# miconborad.net
KiCad netlist of a schematic drawn in EAGLE
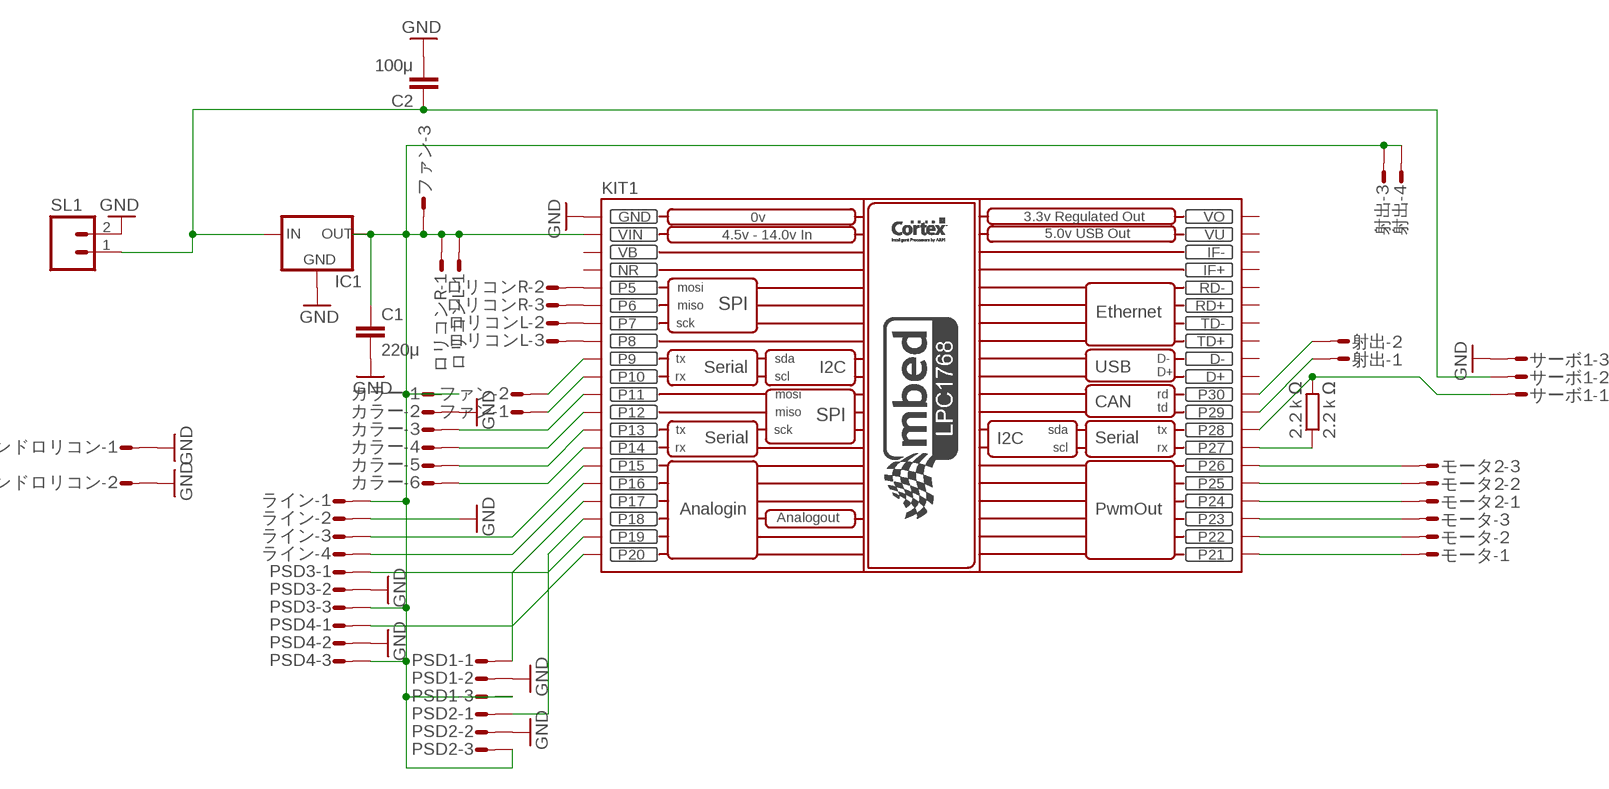
[diagram p0: schematic, sheet 1]

(export (version "E")
  (design (tool "Eeschema 10.0.6"))
  (components
    (comp (ref "2.2ｋΩ")
      (value "2.2ｋΩ")
      (footprint "eagle-import:0204V")
      (libsource (lib "eagle-import") (part "R-EU_0204/2V"))
    )
    (comp (ref "C1")
      (value "220μ")
      (footprint "eagle-import:C025-024X044")
      (libsource (lib "eagle-import") (part "C-EU025-024X044"))
    )
    (comp (ref "C2")
      (value "100μ")
      (footprint "eagle-import:C025-024X044")
      (libsource (lib "eagle-import") (part "C-EU025-024X044"))
    )
    (comp (ref "IC1")
      (value "78XX_V")
      (footprint "eagle-import:78XXV")
      (libsource (lib "eagle-import") (part "78XX_V"))
    )
    (comp (ref "KIT1")
      (value "MBED_NXP_LPC1768")
      (footprint "eagle-import:MBED-KIT")
      (libsource (lib "eagle-import") (part "MBED_NXP_LPC1768"))
    )
    (comp (ref "PSD1")
      (value "S03P")
      (footprint "eagle-import:S03P")
      (libsource (lib "eagle-import") (part "S03P"))
    )
    (comp (ref "PSD2")
      (value "S03P")
      (footprint "eagle-import:S03P")
      (libsource (lib "eagle-import") (part "S03P"))
    )
    (comp (ref "PSD3")
      (value "S03P")
      (footprint "eagle-import:S03P")
      (libsource (lib "eagle-import") (part "S03P"))
    )
    (comp (ref "PSD4")
      (value "S03P")
      (footprint "eagle-import:S03P")
      (libsource (lib "eagle-import") (part "S03P"))
    )
    (comp (ref "SL1")
      (value "M02")
      (footprint "eagle-import:02P")
      (libsource (lib "eagle-import") (part "M02"))
    )
    (comp (ref "カラー")
      (value "S06P")
      (footprint "eagle-import:S06P")
      (libsource (lib "eagle-import") (part "S06P"))
    )
    (comp (ref "グランドロリコン")
      (value "S02P")
      (footprint "eagle-import:S02P")
      (libsource (lib "eagle-import") (part "S02P"))
    )
    (comp (ref "サーボ1")
      (value "S03P")
      (footprint "eagle-import:S03P")
      (libsource (lib "eagle-import") (part "S03P"))
    )
    (comp (ref "ファン")
      (value "S03P")
      (footprint "eagle-import:S03P")
      (libsource (lib "eagle-import") (part "S03P"))
    )
    (comp (ref "モータ")
      (value "S03P")
      (footprint "eagle-import:S03P")
      (libsource (lib "eagle-import") (part "S03P"))
    )
    (comp (ref "モータ2")
      (value "S03P")
      (footprint "eagle-import:S03P")
      (libsource (lib "eagle-import") (part "S03P"))
    )
    (comp (ref "ライン")
      (value "S04P")
      (footprint "eagle-import:S04P")
      (libsource (lib "eagle-import") (part "S04P"))
    )
    (comp (ref "ロリコンL")
      (value "S03P")
      (footprint "eagle-import:S03P")
      (libsource (lib "eagle-import") (part "S03P"))
    )
    (comp (ref "ロリコンR")
      (value "S03P")
      (footprint "eagle-import:S03P")
      (libsource (lib "eagle-import") (part "S03P"))
    )
    (comp (ref "射出")
      (value "S04P")
      (footprint "eagle-import:S04P")
      (libsource (lib "eagle-import") (part "S04P"))
    )
  )
  (nets
    (net (code "1") (name "/NR") (class "Default")
      (node (ref "KIT1") (pin "P$4") (pinfunction "NR_P$4") (pintype "power_in"))
    )
    (net (code "2") (name "/VB") (class "Default")
      (node (ref "KIT1") (pin "P$3") (pinfunction "VB_P$3") (pintype "power_in"))
    )
    (net (code "3") (name "/VO") (class "Default")
      (node (ref "KIT1") (pin "P$40") (pinfunction "VO_P$40") (pintype "power_in"))
    )
    (net (code "4") (name "/VU") (class "Default")
      (node (ref "KIT1") (pin "P$39") (pinfunction "VU_P$39") (pintype "power_in"))
    )
    (net (code "5") (name "GND") (class "Default")
      (node (ref "C1") (pin "2") (pinfunction "2_2") (pintype "passive"))
      (node (ref "C2") (pin "2") (pinfunction "2_2") (pintype "passive"))
      (node (ref "IC1") (pin "GND") (pinfunction "GND_GND") (pintype "input"))
      (node (ref "KIT1") (pin "P$1") (pinfunction "GND_P$1") (pintype "power_in"))
      (node (ref "PSD1") (pin "2") (pinfunction "S_2") (pintype "passive"))
      (node (ref "PSD2") (pin "2") (pinfunction "S_2") (pintype "passive"))
      (node (ref "PSD3") (pin "2") (pinfunction "S_2") (pintype "passive"))
      (node (ref "PSD4") (pin "2") (pinfunction "S_2") (pintype "passive"))
      (node (ref "SL1") (pin "2") (pinfunction "2_2") (pintype "passive"))
      (node (ref "カラー") (pin "2") (pinfunction "S_2") (pintype "passive"))
      (node (ref "グランドロリコン") (pin "1") (pinfunction "S_1") (pintype "passive"))
      (node (ref "グランドロリコン") (pin "2") (pinfunction "S_2") (pintype "passive"))
      (node (ref "サーボ1") (pin "3") (pinfunction "S_3") (pintype "passive"))
      (node (ref "ライン") (pin "2") (pinfunction "S_2") (pintype "passive"))
    )
    (net (code "6") (name "Net-(KIT1-P5)") (class "Default")
      (node (ref "KIT1") (pin "P$5") (pinfunction "P5_P$5") (pintype "bidirectional"))
      (node (ref "ロリコンR") (pin "2") (pinfunction "S_2") (pintype "passive"))
    )
    (net (code "7") (name "Net-(KIT1-P6)") (class "Default")
      (node (ref "KIT1") (pin "P$6") (pinfunction "P6_P$6") (pintype "bidirectional"))
      (node (ref "ロリコンR") (pin "3") (pinfunction "S_3") (pintype "passive"))
    )
    (net (code "8") (name "Net-(KIT1-P7)") (class "Default")
      (node (ref "KIT1") (pin "P$7") (pinfunction "P7_P$7") (pintype "bidirectional"))
      (node (ref "ロリコンL") (pin "2") (pinfunction "S_2") (pintype "passive"))
    )
    (net (code "9") (name "Net-(KIT1-P8)") (class "Default")
      (node (ref "KIT1") (pin "P$8") (pinfunction "P8_P$8") (pintype "bidirectional"))
      (node (ref "ロリコンL") (pin "3") (pinfunction "S_3") (pintype "passive"))
    )
    (net (code "10") (name "Net-(KIT1-P9)") (class "Default")
      (node (ref "KIT1") (pin "P$9") (pinfunction "P9_P$9") (pintype "bidirectional"))
      (node (ref "ファン") (pin "2") (pinfunction "S_2") (pintype "passive"))
    )
    (net (code "11") (name "Net-(KIT1-P10)") (class "Default")
      (node (ref "KIT1") (pin "P$10") (pinfunction "P10_P$10") (pintype "bidirectional"))
      (node (ref "ファン") (pin "1") (pinfunction "S_1") (pintype "passive"))
    )
    (net (code "12") (name "Net-(KIT1-P11)") (class "Default")
      (node (ref "KIT1") (pin "P$11") (pinfunction "P11_P$11") (pintype "bidirectional"))
      (node (ref "カラー") (pin "3") (pinfunction "S_3") (pintype "passive"))
    )
    (net (code "13") (name "Net-(KIT1-P12)") (class "Default")
      (node (ref "KIT1") (pin "P$12") (pinfunction "P12_P$12") (pintype "bidirectional"))
      (node (ref "カラー") (pin "4") (pinfunction "S_4") (pintype "passive"))
    )
    (net (code "14") (name "Net-(KIT1-P13)") (class "Default")
      (node (ref "KIT1") (pin "P$13") (pinfunction "P13_P$13") (pintype "bidirectional"))
      (node (ref "カラー") (pin "5") (pinfunction "S_5") (pintype "passive"))
    )
    (net (code "15") (name "Net-(KIT1-P14)") (class "Default")
      (node (ref "KIT1") (pin "P$14") (pinfunction "P14_P$14") (pintype "bidirectional"))
      (node (ref "カラー") (pin "6") (pinfunction "S_6") (pintype "passive"))
    )
    (net (code "16") (name "Net-(KIT1-P15)") (class "Default")
      (node (ref "KIT1") (pin "P$15") (pinfunction "P15_P$15") (pintype "bidirectional"))
      (node (ref "ライン") (pin "3") (pinfunction "S_3") (pintype "passive"))
    )
    (net (code "17") (name "Net-(KIT1-P16)") (class "Default")
      (node (ref "KIT1") (pin "P$16") (pinfunction "P16_P$16") (pintype "bidirectional"))
      (node (ref "ライン") (pin "4") (pinfunction "S_4") (pintype "passive"))
    )
    (net (code "18") (name "Net-(KIT1-P17)") (class "Default")
      (node (ref "KIT1") (pin "P$17") (pinfunction "P17_P$17") (pintype "bidirectional"))
      (node (ref "PSD1") (pin "1") (pinfunction "S_1") (pintype "passive"))
    )
    (net (code "19") (name "Net-(KIT1-P18)") (class "Default")
      (node (ref "KIT1") (pin "P$18") (pinfunction "P18_P$18") (pintype "bidirectional"))
      (node (ref "PSD2") (pin "1") (pinfunction "S_1") (pintype "passive"))
    )
    (net (code "20") (name "Net-(KIT1-P19)") (class "Default")
      (node (ref "KIT1") (pin "P$19") (pinfunction "P19_P$19") (pintype "bidirectional"))
      (node (ref "PSD3") (pin "1") (pinfunction "S_1") (pintype "passive"))
    )
    (net (code "21") (name "Net-(KIT1-P20)") (class "Default")
      (node (ref "KIT1") (pin "P$20") (pinfunction "P20_P$20") (pintype "bidirectional"))
      (node (ref "PSD4") (pin "1") (pinfunction "S_1") (pintype "passive"))
    )
    (net (code "22") (name "Net-(KIT1-P21)") (class "Default")
      (node (ref "KIT1") (pin "P$21") (pinfunction "P21_P$21") (pintype "bidirectional"))
      (node (ref "モータ") (pin "1") (pinfunction "S_1") (pintype "passive"))
    )
    (net (code "23") (name "Net-(KIT1-P22)") (class "Default")
      (node (ref "KIT1") (pin "P$22") (pinfunction "P22_P$22") (pintype "bidirectional"))
      (node (ref "モータ") (pin "2") (pinfunction "S_2") (pintype "passive"))
    )
    (net (code "24") (name "Net-(KIT1-P23)") (class "Default")
      (node (ref "KIT1") (pin "P$23") (pinfunction "P23_P$23") (pintype "bidirectional"))
      (node (ref "モータ") (pin "3") (pinfunction "S_3") (pintype "passive"))
    )
    (net (code "25") (name "Net-(KIT1-P24)") (class "Default")
      (node (ref "KIT1") (pin "P$24") (pinfunction "P24_P$24") (pintype "bidirectional"))
      (node (ref "モータ2") (pin "1") (pinfunction "S_1") (pintype "passive"))
    )
    (net (code "26") (name "Net-(KIT1-P25)") (class "Default")
      (node (ref "KIT1") (pin "P$25") (pinfunction "P25_P$25") (pintype "bidirectional"))
      (node (ref "モータ2") (pin "2") (pinfunction "S_2") (pintype "passive"))
    )
    (net (code "27") (name "Net-(KIT1-P26)") (class "Default")
      (node (ref "KIT1") (pin "P$26") (pinfunction "P26_P$26") (pintype "bidirectional"))
      (node (ref "モータ2") (pin "3") (pinfunction "S_3") (pintype "passive"))
    )
    (net (code "28") (name "Net-(KIT1-P27)") (class "Default")
      (node (ref "2.2ｋΩ") (pin "1") (pinfunction "1_1") (pintype "passive"))
      (node (ref "KIT1") (pin "P$27") (pinfunction "P27_P$27") (pintype "bidirectional"))
    )
    (net (code "29") (name "Net-(KIT1-P28)") (class "Default")
      (node (ref "2.2ｋΩ") (pin "2") (pinfunction "2_2") (pintype "passive"))
      (node (ref "KIT1") (pin "P$28") (pinfunction "P28_P$28") (pintype "bidirectional"))
      (node (ref "サーボ1") (pin "1") (pinfunction "S_1") (pintype "passive"))
    )
    (net (code "30") (name "Net-(KIT1-P29)") (class "Default")
      (node (ref "KIT1") (pin "P$29") (pinfunction "P29_P$29") (pintype "bidirectional"))
      (node (ref "射出") (pin "1") (pinfunction "S_1") (pintype "passive"))
    )
    (net (code "31") (name "Net-(KIT1-P30)") (class "Default")
      (node (ref "KIT1") (pin "P$30") (pinfunction "P30_P$30") (pintype "bidirectional"))
      (node (ref "射出") (pin "2") (pinfunction "S_2") (pintype "passive"))
    )
    (net (code "32") (name "Net-(KIT1-VIN)") (class "Default")
      (node (ref "C1") (pin "1") (pinfunction "1_1") (pintype "passive"))
      (node (ref "IC1") (pin "OUT") (pinfunction "OUT_OUT") (pintype "passive"))
      (node (ref "KIT1") (pin "P$2") (pinfunction "VIN_P$2") (pintype "power_in"))
      (node (ref "PSD1") (pin "3") (pinfunction "S_3") (pintype "passive"))
      (node (ref "PSD2") (pin "3") (pinfunction "S_3") (pintype "passive"))
      (node (ref "PSD3") (pin "3") (pinfunction "S_3") (pintype "passive"))
      (node (ref "PSD4") (pin "3") (pinfunction "S_3") (pintype "passive"))
      (node (ref "カラー") (pin "1") (pinfunction "S_1") (pintype "passive"))
      (node (ref "ファン") (pin "3") (pinfunction "S_3") (pintype "passive"))
      (node (ref "ライン") (pin "1") (pinfunction "S_1") (pintype "passive"))
      (node (ref "ロリコンL") (pin "1") (pinfunction "S_1") (pintype "passive"))
      (node (ref "ロリコンR") (pin "1") (pinfunction "S_1") (pintype "passive"))
      (node (ref "射出") (pin "3") (pinfunction "S_3") (pintype "passive"))
      (node (ref "射出") (pin "4") (pinfunction "S_4") (pintype "passive"))
    )
    (net (code "33") (name "Net-(サーボ1B-S)") (class "Default")
      (node (ref "C2") (pin "1") (pinfunction "1_1") (pintype "passive"))
      (node (ref "IC1") (pin "IN") (pinfunction "IN_IN") (pintype "input"))
      (node (ref "SL1") (pin "1") (pinfunction "1_1") (pintype "passive"))
      (node (ref "サーボ1") (pin "2") (pinfunction "S_2") (pintype "passive"))
    )
    (net (code "34") (name "unconnected-(KIT1-D+-PadP$31)") (class "Default")
      (node (ref "KIT1") (pin "P$31") (pinfunction "D+_P$31") (pintype "bidirectional"))
    )
    (net (code "35") (name "unconnected-(KIT1-D--PadP$32)") (class "Default")
      (node (ref "KIT1") (pin "P$32") (pinfunction "D-_P$32") (pintype "bidirectional"))
    )
    (net (code "36") (name "unconnected-(KIT1-IF+-PadP$37)") (class "Default")
      (node (ref "KIT1") (pin "P$37") (pinfunction "IF+_P$37") (pintype "bidirectional"))
    )
    (net (code "37") (name "unconnected-(KIT1-IF--PadP$38)") (class "Default")
      (node (ref "KIT1") (pin "P$38") (pinfunction "IF-_P$38") (pintype "bidirectional"))
    )
    (net (code "38") (name "unconnected-(KIT1-RD+-PadP$35)") (class "Default")
      (node (ref "KIT1") (pin "P$35") (pinfunction "RD+_P$35") (pintype "bidirectional"))
    )
    (net (code "39") (name "unconnected-(KIT1-RD--PadP$36)") (class "Default")
      (node (ref "KIT1") (pin "P$36") (pinfunction "RD-_P$36") (pintype "bidirectional"))
    )
    (net (code "40") (name "unconnected-(KIT1-TD+-PadP$33)") (class "Default")
      (node (ref "KIT1") (pin "P$33") (pinfunction "TD+_P$33") (pintype "bidirectional"))
    )
    (net (code "41") (name "unconnected-(KIT1-TD--PadP$34)") (class "Default")
      (node (ref "KIT1") (pin "P$34") (pinfunction "TD-_P$34") (pintype "bidirectional"))
    )
  )
)
